# Perc_soundgen.net
KiCad netlist of a schematic drawn in EAGLE
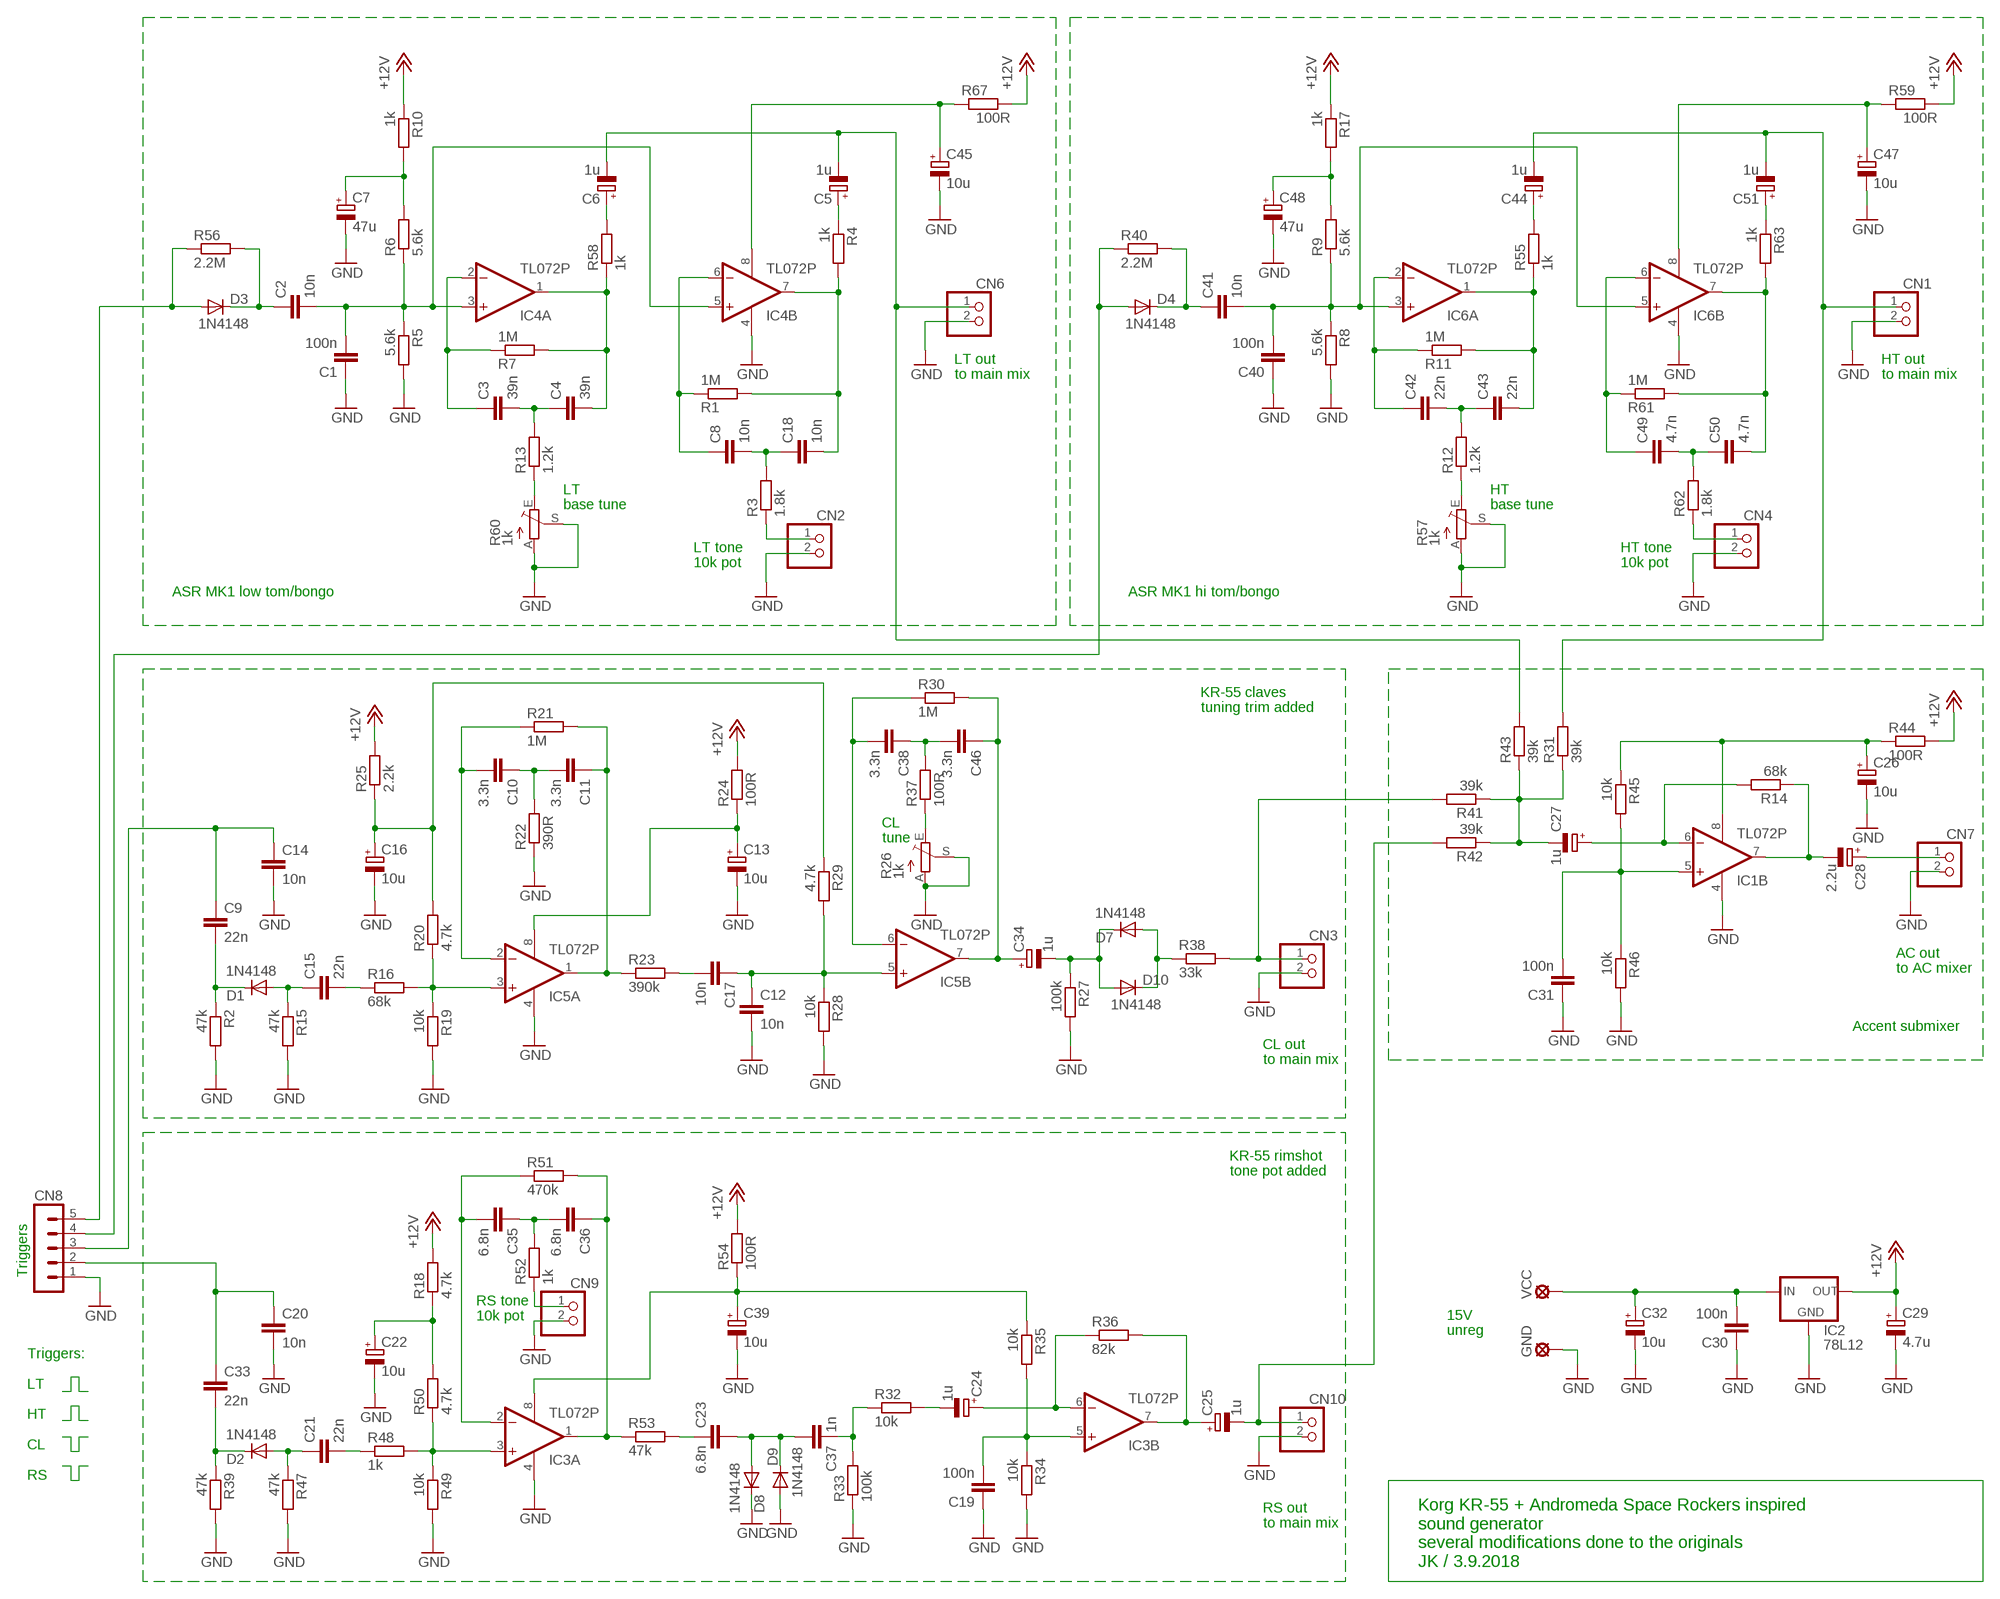
[diagram p0: schematic, sheet 1]

(export (version "E")
  (design (tool "Eeschema 10.0.6"))
  (components
    (comp (ref "C1")
      (value "100n")
      (footprint "eagle-import:C0805")
      (libsource (lib "eagle-import") (part "C-EUC0805"))
    )
    (comp (ref "C2")
      (value "10n")
      (footprint "eagle-import:C0603")
      (libsource (lib "eagle-import") (part "C-EUC0603"))
    )
    (comp (ref "C3")
      (value "39n")
      (footprint "eagle-import:C0805")
      (libsource (lib "eagle-import") (part "C-EUC0805"))
    )
    (comp (ref "C4")
      (value "39n")
      (footprint "eagle-import:C0805")
      (libsource (lib "eagle-import") (part "C-EUC0805"))
    )
    (comp (ref "C5")
      (value "1u")
      (footprint "eagle-import:SMC_A")
      (libsource (lib "eagle-import") (part "CPOL-EUSMCA"))
    )
    (comp (ref "C6")
      (value "1u")
      (footprint "eagle-import:SMC_A")
      (libsource (lib "eagle-import") (part "CPOL-EUSMCA"))
    )
    (comp (ref "C7")
      (value "47u")
      (footprint "eagle-import:E2,5-5")
      (libsource (lib "eagle-import") (part "CPOL-EUE2.5-5"))
    )
    (comp (ref "C8")
      (value "10n")
      (footprint "eagle-import:C0603")
      (libsource (lib "eagle-import") (part "C-EUC0603"))
    )
    (comp (ref "C9")
      (value "22n")
      (footprint "eagle-import:C0805")
      (libsource (lib "eagle-import") (part "C-EUC0805"))
    )
    (comp (ref "C10")
      (value "3.3n")
      (footprint "eagle-import:C0805")
      (libsource (lib "eagle-import") (part "C-EUC0805"))
    )
    (comp (ref "C11")
      (value "3.3n")
      (footprint "eagle-import:C0805")
      (libsource (lib "eagle-import") (part "C-EUC0805"))
    )
    (comp (ref "C12")
      (value "10n")
      (footprint "eagle-import:C0603")
      (libsource (lib "eagle-import") (part "C-EUC0603"))
    )
    (comp (ref "C13")
      (value "10u")
      (footprint "eagle-import:E2,5-5")
      (libsource (lib "eagle-import") (part "CPOL-EUE2.5-5"))
    )
    (comp (ref "C14")
      (value "10n")
      (footprint "eagle-import:C0603")
      (libsource (lib "eagle-import") (part "C-EUC0603"))
    )
    (comp (ref "C15")
      (value "22n")
      (footprint "eagle-import:C0805")
      (libsource (lib "eagle-import") (part "C-EUC0805"))
    )
    (comp (ref "C16")
      (value "10u")
      (footprint "eagle-import:E2,5-5")
      (libsource (lib "eagle-import") (part "CPOL-EUE2.5-5"))
    )
    (comp (ref "C17")
      (value "10n")
      (footprint "eagle-import:C0603")
      (libsource (lib "eagle-import") (part "C-EUC0603"))
    )
    (comp (ref "C18")
      (value "10n")
      (footprint "eagle-import:C0603")
      (libsource (lib "eagle-import") (part "C-EUC0603"))
    )
    (comp (ref "C19")
      (value "100n")
      (footprint "eagle-import:C0805")
      (libsource (lib "eagle-import") (part "C-EUC0805"))
    )
    (comp (ref "C20")
      (value "10n")
      (footprint "eagle-import:C0603")
      (libsource (lib "eagle-import") (part "C-EUC0603"))
    )
    (comp (ref "C21")
      (value "22n")
      (footprint "eagle-import:C0805")
      (libsource (lib "eagle-import") (part "C-EUC0805"))
    )
    (comp (ref "C22")
      (value "10u")
      (footprint "eagle-import:E2,5-5")
      (libsource (lib "eagle-import") (part "CPOL-EUE2.5-5"))
    )
    (comp (ref "C23")
      (value "6.8n")
      (footprint "eagle-import:C0805")
      (libsource (lib "eagle-import") (part "C-EUC0805"))
    )
    (comp (ref "C24")
      (value "1u")
      (footprint "eagle-import:SMC_A")
      (libsource (lib "eagle-import") (part "CPOL-EUSMCA"))
    )
    (comp (ref "C25")
      (value "1u")
      (footprint "eagle-import:SMC_A")
      (libsource (lib "eagle-import") (part "CPOL-EUSMCA"))
    )
    (comp (ref "C26")
      (value "10u")
      (footprint "eagle-import:E2,5-5")
      (libsource (lib "eagle-import") (part "CPOL-EUE2.5-5"))
    )
    (comp (ref "C27")
      (value "1u")
      (footprint "eagle-import:SMC_A")
      (libsource (lib "eagle-import") (part "CPOL-EUSMCA"))
    )
    (comp (ref "C28")
      (value "2.2u")
      (footprint "eagle-import:SMC_A")
      (libsource (lib "eagle-import") (part "CPOL-EUSMCA"))
    )
    (comp (ref "C29")
      (value "4.7u")
      (footprint "eagle-import:SMC_A")
      (libsource (lib "eagle-import") (part "CPOL-EUSMCA"))
    )
    (comp (ref "C30")
      (value "100n")
      (footprint "eagle-import:C0805")
      (libsource (lib "eagle-import") (part "C-EUC0805"))
    )
    (comp (ref "C31")
      (value "100n")
      (footprint "eagle-import:C0805")
      (libsource (lib "eagle-import") (part "C-EUC0805"))
    )
    (comp (ref "C32")
      (value "10u")
      (footprint "eagle-import:E2,5-5")
      (libsource (lib "eagle-import") (part "CPOL-EUE2.5-5"))
    )
    (comp (ref "C33")
      (value "22n")
      (footprint "eagle-import:C075-032X103")
      (libsource (lib "eagle-import") (part "C-EU075-032X103"))
    )
    (comp (ref "C34")
      (value "1u")
      (footprint "eagle-import:SMC_A")
      (libsource (lib "eagle-import") (part "CPOL-EUSMCA"))
    )
    (comp (ref "C35")
      (value "6.8n")
      (footprint "eagle-import:C0805")
      (libsource (lib "eagle-import") (part "C-EUC0805"))
    )
    (comp (ref "C36")
      (value "6.8n")
      (footprint "eagle-import:C0805")
      (libsource (lib "eagle-import") (part "C-EUC0805"))
    )
    (comp (ref "C37")
      (value "1n")
      (footprint "eagle-import:C0805")
      (libsource (lib "eagle-import") (part "C-EUC0805"))
    )
    (comp (ref "C38")
      (value "3.3n")
      (footprint "eagle-import:C0805")
      (libsource (lib "eagle-import") (part "C-EUC0805"))
    )
    (comp (ref "C39")
      (value "10u")
      (footprint "eagle-import:E2,5-5")
      (libsource (lib "eagle-import") (part "CPOL-EUE2.5-5"))
    )
    (comp (ref "C40")
      (value "100n")
      (footprint "eagle-import:C0805")
      (libsource (lib "eagle-import") (part "C-EUC0805"))
    )
    (comp (ref "C41")
      (value "10n")
      (footprint "eagle-import:C0603")
      (libsource (lib "eagle-import") (part "C-EUC0603"))
    )
    (comp (ref "C42")
      (value "22n")
      (footprint "eagle-import:C0805")
      (libsource (lib "eagle-import") (part "C-EUC0805"))
    )
    (comp (ref "C43")
      (value "22n")
      (footprint "eagle-import:C0805")
      (libsource (lib "eagle-import") (part "C-EUC0805"))
    )
    (comp (ref "C44")
      (value "1u")
      (footprint "eagle-import:SMC_A")
      (libsource (lib "eagle-import") (part "CPOL-EUSMCA"))
    )
    (comp (ref "C45")
      (value "10u")
      (footprint "eagle-import:E2,5-5")
      (libsource (lib "eagle-import") (part "CPOL-EUE2.5-5"))
    )
    (comp (ref "C46")
      (value "3.3n")
      (footprint "eagle-import:C0805")
      (libsource (lib "eagle-import") (part "C-EUC0805"))
    )
    (comp (ref "C47")
      (value "10u")
      (footprint "eagle-import:E2,5-5")
      (libsource (lib "eagle-import") (part "CPOL-EUE2.5-5"))
    )
    (comp (ref "C48")
      (value "47u")
      (footprint "eagle-import:E2,5-5")
      (libsource (lib "eagle-import") (part "CPOL-EUE2.5-5"))
    )
    (comp (ref "C49")
      (value "4.7n")
      (footprint "eagle-import:C0805")
      (libsource (lib "eagle-import") (part "C-EUC0805"))
    )
    (comp (ref "C50")
      (value "4.7n")
      (footprint "eagle-import:C0805")
      (libsource (lib "eagle-import") (part "C-EUC0805"))
    )
    (comp (ref "C51")
      (value "1u")
      (footprint "eagle-import:SMC_A")
      (libsource (lib "eagle-import") (part "CPOL-EUSMCA"))
    )
    (comp (ref "CN1")
      (value "PINHD-1X2")
      (footprint "eagle-import:1X02")
      (libsource (lib "eagle-import") (part "PINHD-1X2"))
    )
    (comp (ref "CN2")
      (value "PINHD-1X2")
      (footprint "eagle-import:1X02")
      (libsource (lib "eagle-import") (part "PINHD-1X2"))
    )
    (comp (ref "CN3")
      (value "PINHD-1X2")
      (footprint "eagle-import:1X02")
      (libsource (lib "eagle-import") (part "PINHD-1X2"))
    )
    (comp (ref "CN4")
      (value "PINHD-1X2")
      (footprint "eagle-import:1X02")
      (libsource (lib "eagle-import") (part "PINHD-1X2"))
    )
    (comp (ref "CN6")
      (value "PINHD-1X2")
      (footprint "eagle-import:1X02")
      (libsource (lib "eagle-import") (part "PINHD-1X2"))
    )
    (comp (ref "CN7")
      (value "PINHD-1X2")
      (footprint "eagle-import:1X02")
      (libsource (lib "eagle-import") (part "PINHD-1X2"))
    )
    (comp (ref "CN8")
      (value "MA05-1")
      (footprint "eagle-import:MA05-1")
      (libsource (lib "eagle-import") (part "MA05-1"))
    )
    (comp (ref "CN9")
      (value "PINHD-1X2")
      (footprint "eagle-import:1X02")
      (libsource (lib "eagle-import") (part "PINHD-1X2"))
    )
    (comp (ref "CN10")
      (value "PINHD-1X2")
      (footprint "eagle-import:1X02")
      (libsource (lib "eagle-import") (part "PINHD-1X2"))
    )
    (comp (ref "D1")
      (value "1N4148")
      (footprint "eagle-import:SOD80C")
      (libsource (lib "eagle-import") (part "DIODE-SOD80C"))
    )
    (comp (ref "D2")
      (value "1N4148")
      (footprint "eagle-import:SOD80C")
      (libsource (lib "eagle-import") (part "DIODE-SOD80C"))
    )
    (comp (ref "D3")
      (value "1N4148")
      (footprint "eagle-import:SOD80C")
      (libsource (lib "eagle-import") (part "DIODE-SOD80C"))
    )
    (comp (ref "D4")
      (value "1N4148")
      (footprint "eagle-import:SOD80C")
      (libsource (lib "eagle-import") (part "DIODE-SOD80C"))
    )
    (comp (ref "D7")
      (value "1N4148")
      (footprint "eagle-import:SOD80C")
      (libsource (lib "eagle-import") (part "DIODE-SOD80C"))
    )
    (comp (ref "D8")
      (value "1N4148")
      (footprint "eagle-import:SOD80C")
      (libsource (lib "eagle-import") (part "DIODE-SOD80C"))
    )
    (comp (ref "D9")
      (value "1N4148")
      (footprint "eagle-import:SOD80C")
      (libsource (lib "eagle-import") (part "DIODE-SOD80C"))
    )
    (comp (ref "D10")
      (value "1N4148")
      (footprint "eagle-import:SOD80C")
      (libsource (lib "eagle-import") (part "DIODE-SOD80C"))
    )
    (comp (ref "GND")
      (value "LSP10")
      (footprint "eagle-import:LSP10")
      (libsource (lib "eagle-import") (part "LSP10"))
    )
    (comp (ref "IC1")
      (value "TL072P")
      (footprint "eagle-import:DIL08")
      (libsource (lib "eagle-import") (part "TL072P"))
    )
    (comp (ref "IC2")
      (value "78L12")
      (footprint "eagle-import:78LXX")
      (libsource (lib "eagle-import") (part "78LXX"))
    )
    (comp (ref "IC3")
      (value "TL072P")
      (footprint "eagle-import:DIL08")
      (libsource (lib "eagle-import") (part "TL072P"))
    )
    (comp (ref "IC4")
      (value "TL072P")
      (footprint "eagle-import:DIL08")
      (libsource (lib "eagle-import") (part "TL072P"))
    )
    (comp (ref "IC5")
      (value "TL072P")
      (footprint "eagle-import:DIL08")
      (libsource (lib "eagle-import") (part "TL072P"))
    )
    (comp (ref "IC6")
      (value "TL072P")
      (footprint "eagle-import:DIL08")
      (libsource (lib "eagle-import") (part "TL072P"))
    )
    (comp (ref "R1")
      (value "1M")
      (footprint "eagle-import:R0805")
      (libsource (lib "eagle-import") (part "R-EU_R0805"))
    )
    (comp (ref "R2")
      (value "47k")
      (footprint "eagle-import:R0805")
      (libsource (lib "eagle-import") (part "R-EU_R0805"))
    )
    (comp (ref "R3")
      (value "1.8k")
      (footprint "eagle-import:R0805")
      (libsource (lib "eagle-import") (part "R-EU_R0805"))
    )
    (comp (ref "R4")
      (value "1k")
      (footprint "eagle-import:0207_10")
      (libsource (lib "eagle-import") (part "R-EU_0207/10"))
    )
    (comp (ref "R5")
      (value "5.6k")
      (footprint "eagle-import:R0805")
      (libsource (lib "eagle-import") (part "R-EU_R0805"))
    )
    (comp (ref "R6")
      (value "5.6k")
      (footprint "eagle-import:R0805")
      (libsource (lib "eagle-import") (part "R-EU_R0805"))
    )
    (comp (ref "R7")
      (value "1M")
      (footprint "eagle-import:R0805")
      (libsource (lib "eagle-import") (part "R-EU_R0805"))
    )
    (comp (ref "R8")
      (value "5.6k")
      (footprint "eagle-import:R0805")
      (libsource (lib "eagle-import") (part "R-EU_R0805"))
    )
    (comp (ref "R9")
      (value "5.6k")
      (footprint "eagle-import:R0805")
      (libsource (lib "eagle-import") (part "R-EU_R0805"))
    )
    (comp (ref "R10")
      (value "1k")
      (footprint "eagle-import:R0805")
      (libsource (lib "eagle-import") (part "R-EU_R0805"))
    )
    (comp (ref "R11")
      (value "1M")
      (footprint "eagle-import:R0805")
      (libsource (lib "eagle-import") (part "R-EU_R0805"))
    )
    (comp (ref "R12")
      (value "1.2k")
      (footprint "eagle-import:R0805")
      (libsource (lib "eagle-import") (part "R-EU_R0805"))
    )
    (comp (ref "R13")
      (value "1.2k")
      (footprint "eagle-import:0207_12")
      (libsource (lib "eagle-import") (part "R-EU_0207/12"))
    )
    (comp (ref "R14")
      (value "68k")
      (footprint "eagle-import:R0805")
      (libsource (lib "eagle-import") (part "R-EU_R0805"))
    )
    (comp (ref "R15")
      (value "47k")
      (footprint "eagle-import:R0805")
      (libsource (lib "eagle-import") (part "R-EU_R0805"))
    )
    (comp (ref "R16")
      (value "68k")
      (footprint "eagle-import:R0805")
      (libsource (lib "eagle-import") (part "R-EU_R0805"))
    )
    (comp (ref "R17")
      (value "1k")
      (footprint "eagle-import:R0805")
      (libsource (lib "eagle-import") (part "R-EU_R0805"))
    )
    (comp (ref "R18")
      (value "4.7k")
      (footprint "eagle-import:0207_10")
      (libsource (lib "eagle-import") (part "R-EU_0207/10"))
    )
    (comp (ref "R19")
      (value "10k")
      (footprint "eagle-import:R0805")
      (libsource (lib "eagle-import") (part "R-EU_R0805"))
    )
    (comp (ref "R20")
      (value "4.7k")
      (footprint "eagle-import:R0805")
      (libsource (lib "eagle-import") (part "R-EU_R0805"))
    )
    (comp (ref "R21")
      (value "1M")
      (footprint "eagle-import:R0805")
      (libsource (lib "eagle-import") (part "R-EU_R0805"))
    )
    (comp (ref "R22")
      (value "390R")
      (footprint "eagle-import:R1206")
      (libsource (lib "eagle-import") (part "R-EU_R1206"))
    )
    (comp (ref "R23")
      (value "390k")
      (footprint "eagle-import:0207_10")
      (libsource (lib "eagle-import") (part "R-EU_0207/10"))
    )
    (comp (ref "R24")
      (value "100R")
      (footprint "eagle-import:R0805")
      (libsource (lib "eagle-import") (part "R-EU_R0805"))
    )
    (comp (ref "R25")
      (value "2.2k")
      (footprint "eagle-import:R0805")
      (libsource (lib "eagle-import") (part "R-EU_R0805"))
    )
    (comp (ref "R26")
      (value "1k")
      (footprint "eagle-import:S63X")
      (libsource (lib "eagle-import") (part "TRIM_EU-S63X"))
    )
    (comp (ref "R27")
      (value "100k")
      (footprint "eagle-import:R0805")
      (libsource (lib "eagle-import") (part "R-EU_R0805"))
    )
    (comp (ref "R28")
      (value "10k")
      (footprint "eagle-import:R0805")
      (libsource (lib "eagle-import") (part "R-EU_R0805"))
    )
    (comp (ref "R29")
      (value "4.7k")
      (footprint "eagle-import:0207_10")
      (libsource (lib "eagle-import") (part "R-EU_0207/10"))
    )
    (comp (ref "R30")
      (value "1M")
      (footprint "eagle-import:R0805")
      (libsource (lib "eagle-import") (part "R-EU_R0805"))
    )
    (comp (ref "R31")
      (value "39k")
      (footprint "eagle-import:R0805")
      (libsource (lib "eagle-import") (part "R-EU_R0805"))
    )
    (comp (ref "R32")
      (value "10k")
      (footprint "eagle-import:R0805")
      (libsource (lib "eagle-import") (part "R-EU_R0805"))
    )
    (comp (ref "R33")
      (value "100k")
      (footprint "eagle-import:R0805")
      (libsource (lib "eagle-import") (part "R-EU_R0805"))
    )
    (comp (ref "R34")
      (value "10k")
      (footprint "eagle-import:R0805")
      (libsource (lib "eagle-import") (part "R-EU_R0805"))
    )
    (comp (ref "R35")
      (value "10k")
      (footprint "eagle-import:R0805")
      (libsource (lib "eagle-import") (part "R-EU_R0805"))
    )
    (comp (ref "R36")
      (value "82k")
      (footprint "eagle-import:R0805")
      (libsource (lib "eagle-import") (part "R-EU_R0805"))
    )
    (comp (ref "R37")
      (value "100R")
      (footprint "eagle-import:R0805")
      (libsource (lib "eagle-import") (part "R-EU_R0805"))
    )
    (comp (ref "R38")
      (value "33k")
      (footprint "eagle-import:R0805")
      (libsource (lib "eagle-import") (part "R-EU_R0805"))
    )
    (comp (ref "R39")
      (value "47k")
      (footprint "eagle-import:R0805")
      (libsource (lib "eagle-import") (part "R-EU_R0805"))
    )
    (comp (ref "R40")
      (value "2.2M")
      (footprint "eagle-import:R0805")
      (libsource (lib "eagle-import") (part "R-EU_R0805"))
    )
    (comp (ref "R41")
      (value "39k")
      (footprint "eagle-import:R0805")
      (libsource (lib "eagle-import") (part "R-EU_R0805"))
    )
    (comp (ref "R42")
      (value "39k")
      (footprint "eagle-import:R0805")
      (libsource (lib "eagle-import") (part "R-EU_R0805"))
    )
    (comp (ref "R43")
      (value "39k")
      (footprint "eagle-import:R0805")
      (libsource (lib "eagle-import") (part "R-EU_R0805"))
    )
    (comp (ref "R44")
      (value "100R")
      (footprint "eagle-import:R0805")
      (libsource (lib "eagle-import") (part "R-EU_R0805"))
    )
    (comp (ref "R45")
      (value "10k")
      (footprint "eagle-import:R0805")
      (libsource (lib "eagle-import") (part "R-EU_R0805"))
    )
    (comp (ref "R46")
      (value "10k")
      (footprint "eagle-import:R0805")
      (libsource (lib "eagle-import") (part "R-EU_R0805"))
    )
    (comp (ref "R47")
      (value "47k")
      (footprint "eagle-import:R0805")
      (libsource (lib "eagle-import") (part "R-EU_R0805"))
    )
    (comp (ref "R48")
      (value "1k")
      (footprint "eagle-import:R0805")
      (libsource (lib "eagle-import") (part "R-EU_R0805"))
    )
    (comp (ref "R49")
      (value "10k")
      (footprint "eagle-import:R0805")
      (libsource (lib "eagle-import") (part "R-EU_R0805"))
    )
    (comp (ref "R50")
      (value "4.7k")
      (footprint "eagle-import:R0805")
      (libsource (lib "eagle-import") (part "R-EU_R0805"))
    )
    (comp (ref "R51")
      (value "470k")
      (footprint "eagle-import:R0805")
      (libsource (lib "eagle-import") (part "R-EU_R0805"))
    )
    (comp (ref "R52")
      (value "1k")
      (footprint "eagle-import:R0805")
      (libsource (lib "eagle-import") (part "R-EU_R0805"))
    )
    (comp (ref "R53")
      (value "47k")
      (footprint "eagle-import:0207_10")
      (libsource (lib "eagle-import") (part "R-EU_0207/10"))
    )
    (comp (ref "R54")
      (value "100R")
      (footprint "eagle-import:R0805")
      (libsource (lib "eagle-import") (part "R-EU_R0805"))
    )
    (comp (ref "R55")
      (value "1k")
      (footprint "eagle-import:0207_10")
      (libsource (lib "eagle-import") (part "R-EU_0207/10"))
    )
    (comp (ref "R56")
      (value "2.2M")
      (footprint "eagle-import:R0805")
      (libsource (lib "eagle-import") (part "R-EU_R0805"))
    )
    (comp (ref "R57")
      (value "1k")
      (footprint "eagle-import:S63X")
      (libsource (lib "eagle-import") (part "TRIM_EU-S63X"))
    )
    (comp (ref "R58")
      (value "1k")
      (footprint "eagle-import:0207_10")
      (libsource (lib "eagle-import") (part "R-EU_0207/10"))
    )
    (comp (ref "R59")
      (value "100R")
      (footprint "eagle-import:R0805")
      (libsource (lib "eagle-import") (part "R-EU_R0805"))
    )
    (comp (ref "R60")
      (value "1k")
      (footprint "eagle-import:S63X")
      (libsource (lib "eagle-import") (part "TRIM_EU-S63X"))
    )
    (comp (ref "R61")
      (value "1M")
      (footprint "eagle-import:R0805")
      (libsource (lib "eagle-import") (part "R-EU_R0805"))
    )
    (comp (ref "R62")
      (value "1.8k")
      (footprint "eagle-import:R0805")
      (libsource (lib "eagle-import") (part "R-EU_R0805"))
    )
    (comp (ref "R63")
      (value "1k")
      (footprint "eagle-import:0207_10")
      (libsource (lib "eagle-import") (part "R-EU_0207/10"))
    )
    (comp (ref "R67")
      (value "100R")
      (footprint "eagle-import:R0805")
      (libsource (lib "eagle-import") (part "R-EU_R0805"))
    )
    (comp (ref "VCC")
      (value "LSP10")
      (footprint "eagle-import:LSP10")
      (libsource (lib "eagle-import") (part "LSP10"))
    )
  )
  (nets
    (net (code "1") (name "+12V") (class "Default")
      (node (ref "C29") (pin "+") (pinfunction "+_+") (pintype "passive"))
      (node (ref "IC2") (pin "OUT") (pinfunction "OUT_OUT") (pintype "passive"))
      (node (ref "R10") (pin "1") (pinfunction "1_1") (pintype "passive"))
      (node (ref "R17") (pin "1") (pinfunction "1_1") (pintype "passive"))
      (node (ref "R18") (pin "2") (pinfunction "2_2") (pintype "passive"))
      (node (ref "R24") (pin "2") (pinfunction "2_2") (pintype "passive"))
      (node (ref "R25") (pin "2") (pinfunction "2_2") (pintype "passive"))
      (node (ref "R44") (pin "2") (pinfunction "2_2") (pintype "passive"))
      (node (ref "R54") (pin "2") (pinfunction "2_2") (pintype "passive"))
      (node (ref "R59") (pin "2") (pinfunction "2_2") (pintype "passive"))
      (node (ref "R67") (pin "2") (pinfunction "2_2") (pintype "passive"))
    )
    (net (code "2") (name "GND") (class "Default")
      (node (ref "C1") (pin "1") (pinfunction "1_1") (pintype "passive"))
      (node (ref "C12") (pin "2") (pinfunction "2_2") (pintype "passive"))
      (node (ref "C13") (pin "-") (pinfunction "-_-") (pintype "passive"))
      (node (ref "C14") (pin "2") (pinfunction "2_2") (pintype "passive"))
      (node (ref "C16") (pin "-") (pinfunction "-_-") (pintype "passive"))
      (node (ref "C19") (pin "1") (pinfunction "1_1") (pintype "passive"))
      (node (ref "C20") (pin "2") (pinfunction "2_2") (pintype "passive"))
      (node (ref "C22") (pin "-") (pinfunction "-_-") (pintype "passive"))
      (node (ref "C26") (pin "-") (pinfunction "-_-") (pintype "passive"))
      (node (ref "C29") (pin "-") (pinfunction "-_-") (pintype "passive"))
      (node (ref "C30") (pin "1") (pinfunction "1_1") (pintype "passive"))
      (node (ref "C31") (pin "1") (pinfunction "1_1") (pintype "passive"))
      (node (ref "C32") (pin "-") (pinfunction "-_-") (pintype "passive"))
      (node (ref "C39") (pin "-") (pinfunction "-_-") (pintype "passive"))
      (node (ref "C40") (pin "1") (pinfunction "1_1") (pintype "passive"))
      (node (ref "C45") (pin "-") (pinfunction "-_-") (pintype "passive"))
      (node (ref "C47") (pin "-") (pinfunction "-_-") (pintype "passive"))
      (node (ref "C48") (pin "-") (pinfunction "-_-") (pintype "passive"))
      (node (ref "C7") (pin "-") (pinfunction "-_-") (pintype "passive"))
      (node (ref "CN1") (pin "2") (pinfunction "2_2") (pintype "passive"))
      (node (ref "CN10") (pin "2") (pinfunction "2_2") (pintype "passive"))
      (node (ref "CN2") (pin "2") (pinfunction "2_2") (pintype "passive"))
      (node (ref "CN3") (pin "2") (pinfunction "2_2") (pintype "passive"))
      (node (ref "CN4") (pin "2") (pinfunction "2_2") (pintype "passive"))
      (node (ref "CN6") (pin "2") (pinfunction "2_2") (pintype "passive"))
      (node (ref "CN7") (pin "2") (pinfunction "2_2") (pintype "passive"))
      (node (ref "CN8") (pin "1") (pinfunction "1_1") (pintype "passive"))
      (node (ref "CN9") (pin "2") (pinfunction "2_2") (pintype "passive"))
      (node (ref "D8") (pin "C") (pinfunction "C_C") (pintype "passive"))
      (node (ref "D9") (pin "A") (pinfunction "A_A") (pintype "passive"))
      (node (ref "GND") (pin "MP") (pinfunction "MP_MP") (pintype "passive"))
      (node (ref "IC1") (pin "4") (pinfunction "V-_4") (pintype "power_in"))
      (node (ref "IC2") (pin "GND") (pinfunction "GND_GND") (pintype "input"))
      (node (ref "IC3") (pin "4") (pinfunction "V-_4") (pintype "power_in"))
      (node (ref "IC4") (pin "4") (pinfunction "V-_4") (pintype "power_in"))
      (node (ref "IC5") (pin "4") (pinfunction "V-_4") (pintype "power_in"))
      (node (ref "IC6") (pin "4") (pinfunction "V-_4") (pintype "power_in"))
      (node (ref "R15") (pin "2") (pinfunction "2_2") (pintype "passive"))
      (node (ref "R19") (pin "2") (pinfunction "2_2") (pintype "passive"))
      (node (ref "R2") (pin "2") (pinfunction "2_2") (pintype "passive"))
      (node (ref "R22") (pin "1") (pinfunction "1_1") (pintype "passive"))
      (node (ref "R26") (pin "A") (pinfunction "A_A") (pintype "passive"))
      (node (ref "R26") (pin "S") (pinfunction "S_S") (pintype "passive"))
      (node (ref "R27") (pin "2") (pinfunction "2_2") (pintype "passive"))
      (node (ref "R28") (pin "2") (pinfunction "2_2") (pintype "passive"))
      (node (ref "R33") (pin "1") (pinfunction "1_1") (pintype "passive"))
      (node (ref "R34") (pin "2") (pinfunction "2_2") (pintype "passive"))
      (node (ref "R39") (pin "2") (pinfunction "2_2") (pintype "passive"))
      (node (ref "R46") (pin "2") (pinfunction "2_2") (pintype "passive"))
      (node (ref "R47") (pin "2") (pinfunction "2_2") (pintype "passive"))
      (node (ref "R49") (pin "2") (pinfunction "2_2") (pintype "passive"))
      (node (ref "R5") (pin "2") (pinfunction "2_2") (pintype "passive"))
      (node (ref "R57") (pin "A") (pinfunction "A_A") (pintype "passive"))
      (node (ref "R57") (pin "S") (pinfunction "S_S") (pintype "passive"))
      (node (ref "R60") (pin "A") (pinfunction "A_A") (pintype "passive"))
      (node (ref "R60") (pin "S") (pinfunction "S_S") (pintype "passive"))
      (node (ref "R8") (pin "2") (pinfunction "2_2") (pintype "passive"))
    )
    (net (code "3") (name "Net-(C2-Pad1)") (class "Default")
      (node (ref "C2") (pin "1") (pinfunction "1_1") (pintype "passive"))
      (node (ref "D3") (pin "C") (pinfunction "C_C") (pintype "passive"))
      (node (ref "R56") (pin "2") (pinfunction "2_2") (pintype "passive"))
    )
    (net (code "4") (name "Net-(C3-Pad2)") (class "Default")
      (node (ref "C3") (pin "2") (pinfunction "2_2") (pintype "passive"))
      (node (ref "C4") (pin "1") (pinfunction "1_1") (pintype "passive"))
      (node (ref "R13") (pin "2") (pinfunction "2_2") (pintype "passive"))
    )
    (net (code "5") (name "Net-(C5-Pad+)") (class "Default")
      (node (ref "C5") (pin "+") (pinfunction "+_+") (pintype "passive"))
      (node (ref "R4") (pin "1") (pinfunction "1_1") (pintype "passive"))
    )
    (net (code "6") (name "Net-(C5-Pad-)") (class "Default")
      (node (ref "C5") (pin "-") (pinfunction "-_-") (pintype "passive"))
      (node (ref "C6") (pin "-") (pinfunction "-_-") (pintype "passive"))
      (node (ref "CN6") (pin "1") (pinfunction "1_1") (pintype "passive"))
      (node (ref "R43") (pin "2") (pinfunction "2_2") (pintype "passive"))
    )
    (net (code "7") (name "Net-(C6-Pad+)") (class "Default")
      (node (ref "C6") (pin "+") (pinfunction "+_+") (pintype "passive"))
      (node (ref "R58") (pin "2") (pinfunction "2_2") (pintype "passive"))
    )
    (net (code "8") (name "Net-(C7-Pad+)") (class "Default")
      (node (ref "C7") (pin "+") (pinfunction "+_+") (pintype "passive"))
      (node (ref "R10") (pin "2") (pinfunction "2_2") (pintype "passive"))
      (node (ref "R6") (pin "2") (pinfunction "2_2") (pintype "passive"))
    )
    (net (code "9") (name "Net-(C9-Pad2)") (class "Default")
      (node (ref "C9") (pin "2") (pinfunction "2_2") (pintype "passive"))
      (node (ref "D1") (pin "C") (pinfunction "C_C") (pintype "passive"))
      (node (ref "R2") (pin "1") (pinfunction "1_1") (pintype "passive"))
    )
    (net (code "10") (name "Net-(C10-Pad1)") (class "Default")
      (node (ref "C10") (pin "1") (pinfunction "1_1") (pintype "passive"))
      (node (ref "C11") (pin "2") (pinfunction "2_2") (pintype "passive"))
      (node (ref "R22") (pin "2") (pinfunction "2_2") (pintype "passive"))
    )
    (net (code "11") (name "Net-(C14-Pad1)") (class "Default")
      (node (ref "C14") (pin "1") (pinfunction "1_1") (pintype "passive"))
      (node (ref "C9") (pin "1") (pinfunction "1_1") (pintype "passive"))
      (node (ref "CN8") (pin "3") (pinfunction "3_3") (pintype "passive"))
    )
    (net (code "12") (name "Net-(C15-Pad1)") (class "Default")
      (node (ref "C15") (pin "1") (pinfunction "1_1") (pintype "passive"))
      (node (ref "D1") (pin "A") (pinfunction "A_A") (pintype "passive"))
      (node (ref "R15") (pin "1") (pinfunction "1_1") (pintype "passive"))
    )
    (net (code "13") (name "Net-(C15-Pad2)") (class "Default")
      (node (ref "C15") (pin "2") (pinfunction "2_2") (pintype "passive"))
      (node (ref "R16") (pin "1") (pinfunction "1_1") (pintype "passive"))
    )
    (net (code "14") (name "Net-(C16-Pad+)") (class "Default")
      (node (ref "C16") (pin "+") (pinfunction "+_+") (pintype "passive"))
      (node (ref "R20") (pin "2") (pinfunction "2_2") (pintype "passive"))
      (node (ref "R25") (pin "1") (pinfunction "1_1") (pintype "passive"))
      (node (ref "R29") (pin "1") (pinfunction "1_1") (pintype "passive"))
    )
    (net (code "15") (name "Net-(C17-Pad2)") (class "Default")
      (node (ref "C17") (pin "2") (pinfunction "2_2") (pintype "passive"))
      (node (ref "R23") (pin "2") (pinfunction "2_2") (pintype "passive"))
    )
    (net (code "16") (name "Net-(C18-Pad1)") (class "Default")
      (node (ref "C18") (pin "1") (pinfunction "1_1") (pintype "passive"))
      (node (ref "C8") (pin "2") (pinfunction "2_2") (pintype "passive"))
      (node (ref "R3") (pin "2") (pinfunction "2_2") (pintype "passive"))
    )
    (net (code "17") (name "Net-(C20-Pad1)") (class "Default")
      (node (ref "C20") (pin "1") (pinfunction "1_1") (pintype "passive"))
      (node (ref "C33") (pin "1") (pinfunction "1_1") (pintype "passive"))
      (node (ref "CN8") (pin "2") (pinfunction "2_2") (pintype "passive"))
    )
    (net (code "18") (name "Net-(C21-Pad1)") (class "Default")
      (node (ref "C21") (pin "1") (pinfunction "1_1") (pintype "passive"))
      (node (ref "D2") (pin "A") (pinfunction "A_A") (pintype "passive"))
      (node (ref "R47") (pin "1") (pinfunction "1_1") (pintype "passive"))
    )
    (net (code "19") (name "Net-(C21-Pad2)") (class "Default")
      (node (ref "C21") (pin "2") (pinfunction "2_2") (pintype "passive"))
      (node (ref "R48") (pin "1") (pinfunction "1_1") (pintype "passive"))
    )
    (net (code "20") (name "Net-(C22-Pad+)") (class "Default")
      (node (ref "C22") (pin "+") (pinfunction "+_+") (pintype "passive"))
      (node (ref "R18") (pin "1") (pinfunction "1_1") (pintype "passive"))
      (node (ref "R50") (pin "2") (pinfunction "2_2") (pintype "passive"))
    )
    (net (code "21") (name "Net-(C23-Pad1)") (class "Default")
      (node (ref "C23") (pin "1") (pinfunction "1_1") (pintype "passive"))
      (node (ref "C37") (pin "2") (pinfunction "2_2") (pintype "passive"))
      (node (ref "D8") (pin "A") (pinfunction "A_A") (pintype "passive"))
      (node (ref "D9") (pin "C") (pinfunction "C_C") (pintype "passive"))
    )
    (net (code "22") (name "Net-(C23-Pad2)") (class "Default")
      (node (ref "C23") (pin "2") (pinfunction "2_2") (pintype "passive"))
      (node (ref "R53") (pin "2") (pinfunction "2_2") (pintype "passive"))
    )
    (net (code "23") (name "Net-(C24-Pad-)") (class "Default")
      (node (ref "C24") (pin "-") (pinfunction "-_-") (pintype "passive"))
      (node (ref "R32") (pin "2") (pinfunction "2_2") (pintype "passive"))
    )
    (net (code "24") (name "Net-(C25-Pad-)") (class "Default")
      (node (ref "C25") (pin "-") (pinfunction "-_-") (pintype "passive"))
      (node (ref "CN10") (pin "1") (pinfunction "1_1") (pintype "passive"))
      (node (ref "R42") (pin "2") (pinfunction "2_2") (pintype "passive"))
    )
    (net (code "25") (name "Net-(C27-Pad-)") (class "Default")
      (node (ref "C27") (pin "-") (pinfunction "-_-") (pintype "passive"))
      (node (ref "R31") (pin "1") (pinfunction "1_1") (pintype "passive"))
      (node (ref "R41") (pin "1") (pinfunction "1_1") (pintype "passive"))
      (node (ref "R42") (pin "1") (pinfunction "1_1") (pintype "passive"))
      (node (ref "R43") (pin "1") (pinfunction "1_1") (pintype "passive"))
    )
    (net (code "26") (name "Net-(C28-Pad+)") (class "Default")
      (node (ref "C28") (pin "+") (pinfunction "+_+") (pintype "passive"))
      (node (ref "CN7") (pin "1") (pinfunction "1_1") (pintype "passive"))
    )
    (net (code "27") (name "Net-(C30-Pad2)") (class "Default")
      (node (ref "C30") (pin "2") (pinfunction "2_2") (pintype "passive"))
      (node (ref "C32") (pin "+") (pinfunction "+_+") (pintype "passive"))
      (node (ref "IC2") (pin "IN") (pinfunction "IN_IN") (pintype "input"))
      (node (ref "VCC") (pin "MP") (pinfunction "MP_MP") (pintype "passive"))
    )
    (net (code "28") (name "Net-(C33-Pad2)") (class "Default")
      (node (ref "C33") (pin "2") (pinfunction "2_2") (pintype "passive"))
      (node (ref "D2") (pin "C") (pinfunction "C_C") (pintype "passive"))
      (node (ref "R39") (pin "1") (pinfunction "1_1") (pintype "passive"))
    )
    (net (code "29") (name "Net-(C34-Pad-)") (class "Default")
      (node (ref "C34") (pin "-") (pinfunction "-_-") (pintype "passive"))
      (node (ref "D10") (pin "A") (pinfunction "A_A") (pintype "passive"))
      (node (ref "D7") (pin "C") (pinfunction "C_C") (pintype "passive"))
      (node (ref "R27") (pin "1") (pinfunction "1_1") (pintype "passive"))
    )
    (net (code "30") (name "Net-(C35-Pad1)") (class "Default")
      (node (ref "C35") (pin "1") (pinfunction "1_1") (pintype "passive"))
      (node (ref "C36") (pin "2") (pinfunction "2_2") (pintype "passive"))
      (node (ref "R52") (pin "2") (pinfunction "2_2") (pintype "passive"))
    )
    (net (code "31") (name "Net-(C37-Pad1)") (class "Default")
      (node (ref "C37") (pin "1") (pinfunction "1_1") (pintype "passive"))
      (node (ref "R32") (pin "1") (pinfunction "1_1") (pintype "passive"))
      (node (ref "R33") (pin "2") (pinfunction "2_2") (pintype "passive"))
    )
    (net (code "32") (name "Net-(C38-Pad1)") (class "Default")
      (node (ref "C38") (pin "1") (pinfunction "1_1") (pintype "passive"))
      (node (ref "C46") (pin "2") (pinfunction "2_2") (pintype "passive"))
      (node (ref "R37") (pin "2") (pinfunction "2_2") (pintype "passive"))
    )
    (net (code "33") (name "Net-(C41-Pad1)") (class "Default")
      (node (ref "C41") (pin "1") (pinfunction "1_1") (pintype "passive"))
      (node (ref "D4") (pin "C") (pinfunction "C_C") (pintype "passive"))
      (node (ref "R40") (pin "2") (pinfunction "2_2") (pintype "passive"))
    )
    (net (code "34") (name "Net-(C42-Pad2)") (class "Default")
      (node (ref "C42") (pin "2") (pinfunction "2_2") (pintype "passive"))
      (node (ref "C43") (pin "1") (pinfunction "1_1") (pintype "passive"))
      (node (ref "R12") (pin "2") (pinfunction "2_2") (pintype "passive"))
    )
    (net (code "35") (name "Net-(C44-Pad+)") (class "Default")
      (node (ref "C44") (pin "+") (pinfunction "+_+") (pintype "passive"))
      (node (ref "R55") (pin "2") (pinfunction "2_2") (pintype "passive"))
    )
    (net (code "36") (name "Net-(C44-Pad-)") (class "Default")
      (node (ref "C44") (pin "-") (pinfunction "-_-") (pintype "passive"))
      (node (ref "C51") (pin "-") (pinfunction "-_-") (pintype "passive"))
      (node (ref "CN1") (pin "1") (pinfunction "1_1") (pintype "passive"))
      (node (ref "R31") (pin "2") (pinfunction "2_2") (pintype "passive"))
    )
    (net (code "37") (name "Net-(C48-Pad+)") (class "Default")
      (node (ref "C48") (pin "+") (pinfunction "+_+") (pintype "passive"))
      (node (ref "R17") (pin "2") (pinfunction "2_2") (pintype "passive"))
      (node (ref "R9") (pin "2") (pinfunction "2_2") (pintype "passive"))
    )
    (net (code "38") (name "Net-(C49-Pad2)") (class "Default")
      (node (ref "C49") (pin "2") (pinfunction "2_2") (pintype "passive"))
      (node (ref "C50") (pin "1") (pinfunction "1_1") (pintype "passive"))
      (node (ref "R62") (pin "2") (pinfunction "2_2") (pintype "passive"))
    )
    (net (code "39") (name "Net-(C51-Pad+)") (class "Default")
      (node (ref "C51") (pin "+") (pinfunction "+_+") (pintype "passive"))
      (node (ref "R63") (pin "1") (pinfunction "1_1") (pintype "passive"))
    )
    (net (code "40") (name "Net-(CN2-Pad1)") (class "Default")
      (node (ref "CN2") (pin "1") (pinfunction "1_1") (pintype "passive"))
      (node (ref "R3") (pin "1") (pinfunction "1_1") (pintype "passive"))
    )
    (net (code "41") (name "Net-(CN3-Pad1)") (class "Default")
      (node (ref "CN3") (pin "1") (pinfunction "1_1") (pintype "passive"))
      (node (ref "R38") (pin "2") (pinfunction "2_2") (pintype "passive"))
      (node (ref "R41") (pin "2") (pinfunction "2_2") (pintype "passive"))
    )
    (net (code "42") (name "Net-(CN4-Pad1)") (class "Default")
      (node (ref "CN4") (pin "1") (pinfunction "1_1") (pintype "passive"))
      (node (ref "R62") (pin "1") (pinfunction "1_1") (pintype "passive"))
    )
    (net (code "43") (name "Net-(CN8-Pad4)") (class "Default")
      (node (ref "CN8") (pin "4") (pinfunction "4_4") (pintype "passive"))
      (node (ref "D4") (pin "A") (pinfunction "A_A") (pintype "passive"))
      (node (ref "R40") (pin "1") (pinfunction "1_1") (pintype "passive"))
    )
    (net (code "44") (name "Net-(CN8-Pad5)") (class "Default")
      (node (ref "CN8") (pin "5") (pinfunction "5_5") (pintype "passive"))
      (node (ref "D3") (pin "A") (pinfunction "A_A") (pintype "passive"))
      (node (ref "R56") (pin "1") (pinfunction "1_1") (pintype "passive"))
    )
    (net (code "45") (name "Net-(CN9-Pad1)") (class "Default")
      (node (ref "CN9") (pin "1") (pinfunction "1_1") (pintype "passive"))
      (node (ref "R52") (pin "1") (pinfunction "1_1") (pintype "passive"))
    )
    (net (code "46") (name "Net-(D10-PadC)") (class "Default")
      (node (ref "D10") (pin "C") (pinfunction "C_C") (pintype "passive"))
      (node (ref "D7") (pin "A") (pinfunction "A_A") (pintype "passive"))
      (node (ref "R38") (pin "1") (pinfunction "1_1") (pintype "passive"))
    )
    (net (code "47") (name "Net-(IC1B-+IN)") (class "Default")
      (node (ref "C31") (pin "2") (pinfunction "2_2") (pintype "passive"))
      (node (ref "IC1") (pin "5") (pinfunction "+IN_5") (pintype "input"))
      (node (ref "R45") (pin "2") (pinfunction "2_2") (pintype "passive"))
      (node (ref "R46") (pin "1") (pinfunction "1_1") (pintype "passive"))
    )
    (net (code "48") (name "Net-(IC1B--IN)") (class "Default")
      (node (ref "C27") (pin "+") (pinfunction "+_+") (pintype "passive"))
      (node (ref "IC1") (pin "6") (pinfunction "-IN_6") (pintype "input"))
      (node (ref "R14") (pin "2") (pinfunction "2_2") (pintype "passive"))
    )
    (net (code "49") (name "Net-(IC1B-OUT)") (class "Default")
      (node (ref "C28") (pin "-") (pinfunction "-_-") (pintype "passive"))
      (node (ref "IC1") (pin "7") (pinfunction "OUT_7") (pintype "output"))
      (node (ref "R14") (pin "1") (pinfunction "1_1") (pintype "passive"))
    )
    (net (code "50") (name "Net-(IC1C-V+)") (class "Default")
      (node (ref "C26") (pin "+") (pinfunction "+_+") (pintype "passive"))
      (node (ref "IC1") (pin "8") (pinfunction "V+_8") (pintype "power_in"))
      (node (ref "R44") (pin "1") (pinfunction "1_1") (pintype "passive"))
      (node (ref "R45") (pin "1") (pinfunction "1_1") (pintype "passive"))
    )
    (net (code "51") (name "Net-(IC3A-+IN)") (class "Default")
      (node (ref "IC3") (pin "3") (pinfunction "+IN_3") (pintype "input"))
      (node (ref "R48") (pin "2") (pinfunction "2_2") (pintype "passive"))
      (node (ref "R49") (pin "1") (pinfunction "1_1") (pintype "passive"))
      (node (ref "R50") (pin "1") (pinfunction "1_1") (pintype "passive"))
    )
    (net (code "52") (name "Net-(IC3A--IN)") (class "Default")
      (node (ref "C35") (pin "2") (pinfunction "2_2") (pintype "passive"))
      (node (ref "IC3") (pin "2") (pinfunction "-IN_2") (pintype "input"))
      (node (ref "R51") (pin "1") (pinfunction "1_1") (pintype "passive"))
    )
    (net (code "53") (name "Net-(IC3A-OUT)") (class "Default")
      (node (ref "C36") (pin "1") (pinfunction "1_1") (pintype "passive"))
      (node (ref "IC3") (pin "1") (pinfunction "OUT_1") (pintype "output"))
      (node (ref "R51") (pin "2") (pinfunction "2_2") (pintype "passive"))
      (node (ref "R53") (pin "1") (pinfunction "1_1") (pintype "passive"))
    )
    (net (code "54") (name "Net-(IC3B-+IN)") (class "Default")
      (node (ref "C19") (pin "2") (pinfunction "2_2") (pintype "passive"))
      (node (ref "IC3") (pin "5") (pinfunction "+IN_5") (pintype "input"))
      (node (ref "R34") (pin "1") (pinfunction "1_1") (pintype "passive"))
      (node (ref "R35") (pin "2") (pinfunction "2_2") (pintype "passive"))
    )
    (net (code "55") (name "Net-(IC3B--IN)") (class "Default")
      (node (ref "C24") (pin "+") (pinfunction "+_+") (pintype "passive"))
      (node (ref "IC3") (pin "6") (pinfunction "-IN_6") (pintype "input"))
      (node (ref "R36") (pin "1") (pinfunction "1_1") (pintype "passive"))
    )
    (net (code "56") (name "Net-(IC3B-OUT)") (class "Default")
      (node (ref "C25") (pin "+") (pinfunction "+_+") (pintype "passive"))
      (node (ref "IC3") (pin "7") (pinfunction "OUT_7") (pintype "output"))
      (node (ref "R36") (pin "2") (pinfunction "2_2") (pintype "passive"))
    )
    (net (code "57") (name "Net-(IC3C-V+)") (class "Default")
      (node (ref "C39") (pin "+") (pinfunction "+_+") (pintype "passive"))
      (node (ref "IC3") (pin "8") (pinfunction "V+_8") (pintype "power_in"))
      (node (ref "R35") (pin "1") (pinfunction "1_1") (pintype "passive"))
      (node (ref "R54") (pin "1") (pinfunction "1_1") (pintype "passive"))
    )
    (net (code "58") (name "Net-(IC4A-+IN)") (class "Default")
      (node (ref "C1") (pin "2") (pinfunction "2_2") (pintype "passive"))
      (node (ref "C2") (pin "2") (pinfunction "2_2") (pintype "passive"))
      (node (ref "IC4") (pin "3") (pinfunction "+IN_3") (pintype "input"))
      (node (ref "IC4") (pin "5") (pinfunction "+IN_5") (pintype "input"))
      (node (ref "R5") (pin "1") (pinfunction "1_1") (pintype "passive"))
      (node (ref "R6") (pin "1") (pinfunction "1_1") (pintype "passive"))
    )
    (net (code "59") (name "Net-(IC4A--IN)") (class "Default")
      (node (ref "C3") (pin "1") (pinfunction "1_1") (pintype "passive"))
      (node (ref "IC4") (pin "2") (pinfunction "-IN_2") (pintype "input"))
      (node (ref "R7") (pin "1") (pinfunction "1_1") (pintype "passive"))
    )
    (net (code "60") (name "Net-(IC4A-OUT)") (class "Default")
      (node (ref "C4") (pin "2") (pinfunction "2_2") (pintype "passive"))
      (node (ref "IC4") (pin "1") (pinfunction "OUT_1") (pintype "output"))
      (node (ref "R58") (pin "1") (pinfunction "1_1") (pintype "passive"))
      (node (ref "R7") (pin "2") (pinfunction "2_2") (pintype "passive"))
    )
    (net (code "61") (name "Net-(IC4B--IN)") (class "Default")
      (node (ref "C8") (pin "1") (pinfunction "1_1") (pintype "passive"))
      (node (ref "IC4") (pin "6") (pinfunction "-IN_6") (pintype "input"))
      (node (ref "R1") (pin "1") (pinfunction "1_1") (pintype "passive"))
    )
    (net (code "62") (name "Net-(IC4B-OUT)") (class "Default")
      (node (ref "C18") (pin "2") (pinfunction "2_2") (pintype "passive"))
      (node (ref "IC4") (pin "7") (pinfunction "OUT_7") (pintype "output"))
      (node (ref "R1") (pin "2") (pinfunction "2_2") (pintype "passive"))
      (node (ref "R4") (pin "2") (pinfunction "2_2") (pintype "passive"))
    )
    (net (code "63") (name "Net-(IC4C-V+)") (class "Default")
      (node (ref "C45") (pin "+") (pinfunction "+_+") (pintype "passive"))
      (node (ref "IC4") (pin "8") (pinfunction "V+_8") (pintype "power_in"))
      (node (ref "R67") (pin "1") (pinfunction "1_1") (pintype "passive"))
    )
    (net (code "64") (name "Net-(IC5A-+IN)") (class "Default")
      (node (ref "IC5") (pin "3") (pinfunction "+IN_3") (pintype "input"))
      (node (ref "R16") (pin "2") (pinfunction "2_2") (pintype "passive"))
      (node (ref "R19") (pin "1") (pinfunction "1_1") (pintype "passive"))
      (node (ref "R20") (pin "1") (pinfunction "1_1") (pintype "passive"))
    )
    (net (code "65") (name "Net-(IC5A--IN)") (class "Default")
      (node (ref "C10") (pin "2") (pinfunction "2_2") (pintype "passive"))
      (node (ref "IC5") (pin "2") (pinfunction "-IN_2") (pintype "input"))
      (node (ref "R21") (pin "1") (pinfunction "1_1") (pintype "passive"))
    )
    (net (code "66") (name "Net-(IC5A-OUT)") (class "Default")
      (node (ref "C11") (pin "1") (pinfunction "1_1") (pintype "passive"))
      (node (ref "IC5") (pin "1") (pinfunction "OUT_1") (pintype "output"))
      (node (ref "R21") (pin "2") (pinfunction "2_2") (pintype "passive"))
      (node (ref "R23") (pin "1") (pinfunction "1_1") (pintype "passive"))
    )
    (net (code "67") (name "Net-(IC5B-+IN)") (class "Default")
      (node (ref "C12") (pin "1") (pinfunction "1_1") (pintype "passive"))
      (node (ref "C17") (pin "1") (pinfunction "1_1") (pintype "passive"))
      (node (ref "IC5") (pin "5") (pinfunction "+IN_5") (pintype "input"))
      (node (ref "R28") (pin "1") (pinfunction "1_1") (pintype "passive"))
      (node (ref "R29") (pin "2") (pinfunction "2_2") (pintype "passive"))
    )
    (net (code "68") (name "Net-(IC5B--IN)") (class "Default")
      (node (ref "C38") (pin "2") (pinfunction "2_2") (pintype "passive"))
      (node (ref "IC5") (pin "6") (pinfunction "-IN_6") (pintype "input"))
      (node (ref "R30") (pin "1") (pinfunction "1_1") (pintype "passive"))
    )
    (net (code "69") (name "Net-(IC5B-OUT)") (class "Default")
      (node (ref "C34") (pin "+") (pinfunction "+_+") (pintype "passive"))
      (node (ref "C46") (pin "1") (pinfunction "1_1") (pintype "passive"))
      (node (ref "IC5") (pin "7") (pinfunction "OUT_7") (pintype "output"))
      (node (ref "R30") (pin "2") (pinfunction "2_2") (pintype "passive"))
    )
    (net (code "70") (name "Net-(IC5C-V+)") (class "Default")
      (node (ref "C13") (pin "+") (pinfunction "+_+") (pintype "passive"))
      (node (ref "IC5") (pin "8") (pinfunction "V+_8") (pintype "power_in"))
      (node (ref "R24") (pin "1") (pinfunction "1_1") (pintype "passive"))
    )
    (net (code "71") (name "Net-(IC6A-+IN)") (class "Default")
      (node (ref "C40") (pin "2") (pinfunction "2_2") (pintype "passive"))
      (node (ref "C41") (pin "2") (pinfunction "2_2") (pintype "passive"))
      (node (ref "IC6") (pin "3") (pinfunction "+IN_3") (pintype "input"))
      (node (ref "IC6") (pin "5") (pinfunction "+IN_5") (pintype "input"))
      (node (ref "R8") (pin "1") (pinfunction "1_1") (pintype "passive"))
      (node (ref "R9") (pin "1") (pinfunction "1_1") (pintype "passive"))
    )
    (net (code "72") (name "Net-(IC6A--IN)") (class "Default")
      (node (ref "C42") (pin "1") (pinfunction "1_1") (pintype "passive"))
      (node (ref "IC6") (pin "2") (pinfunction "-IN_2") (pintype "input"))
      (node (ref "R11") (pin "1") (pinfunction "1_1") (pintype "passive"))
    )
    (net (code "73") (name "Net-(IC6A-OUT)") (class "Default")
      (node (ref "C43") (pin "2") (pinfunction "2_2") (pintype "passive"))
      (node (ref "IC6") (pin "1") (pinfunction "OUT_1") (pintype "output"))
      (node (ref "R11") (pin "2") (pinfunction "2_2") (pintype "passive"))
      (node (ref "R55") (pin "1") (pinfunction "1_1") (pintype "passive"))
    )
    (net (code "74") (name "Net-(IC6B--IN)") (class "Default")
      (node (ref "C49") (pin "1") (pinfunction "1_1") (pintype "passive"))
      (node (ref "IC6") (pin "6") (pinfunction "-IN_6") (pintype "input"))
      (node (ref "R61") (pin "1") (pinfunction "1_1") (pintype "passive"))
    )
    (net (code "75") (name "Net-(IC6B-OUT)") (class "Default")
      (node (ref "C50") (pin "2") (pinfunction "2_2") (pintype "passive"))
      (node (ref "IC6") (pin "7") (pinfunction "OUT_7") (pintype "output"))
      (node (ref "R61") (pin "2") (pinfunction "2_2") (pintype "passive"))
      (node (ref "R63") (pin "2") (pinfunction "2_2") (pintype "passive"))
    )
    (net (code "76") (name "Net-(IC6C-V+)") (class "Default")
      (node (ref "C47") (pin "+") (pinfunction "+_+") (pintype "passive"))
      (node (ref "IC6") (pin "8") (pinfunction "V+_8") (pintype "power_in"))
      (node (ref "R59") (pin "1") (pinfunction "1_1") (pintype "passive"))
    )
    (net (code "77") (name "Net-(R12-Pad1)") (class "Default")
      (node (ref "R12") (pin "1") (pinfunction "1_1") (pintype "passive"))
      (node (ref "R57") (pin "E") (pinfunction "E_E") (pintype "passive"))
    )
    (net (code "78") (name "Net-(R13-Pad1)") (class "Default")
      (node (ref "R13") (pin "1") (pinfunction "1_1") (pintype "passive"))
      (node (ref "R60") (pin "E") (pinfunction "E_E") (pintype "passive"))
    )
    (net (code "79") (name "Net-(R26-PadE)") (class "Default")
      (node (ref "R26") (pin "E") (pinfunction "E_E") (pintype "passive"))
      (node (ref "R37") (pin "1") (pinfunction "1_1") (pintype "passive"))
    )
  )
)
